# drums.net
KiCad netlist of a schematic drawn in EAGLE
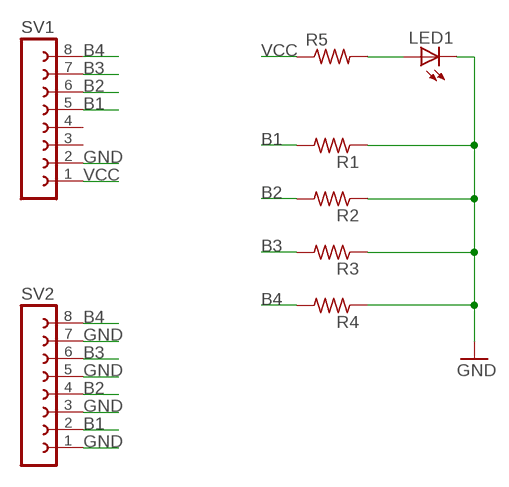
[diagram p0: schematic, sheet 1]

(export (version "E")
  (design (tool "Eeschema 10.0.6"))
  (components
    (comp (ref "LED1")
      (value "LED5MM")
      (footprint "eagle-import:LED5MM")
      (libsource (lib "eagle-import") (part "LED5MM"))
    )
    (comp (ref "R1")
      (value "R-US_0207/7")
      (footprint "eagle-import:0207_7")
      (libsource (lib "eagle-import") (part "R-US_0207/7"))
    )
    (comp (ref "R2")
      (value "R-US_0207/7")
      (footprint "eagle-import:0207_7")
      (libsource (lib "eagle-import") (part "R-US_0207/7"))
    )
    (comp (ref "R3")
      (value "R-US_0207/7")
      (footprint "eagle-import:0207_7")
      (libsource (lib "eagle-import") (part "R-US_0207/7"))
    )
    (comp (ref "R4")
      (value "R-US_0207/7")
      (footprint "eagle-import:0207_7")
      (libsource (lib "eagle-import") (part "R-US_0207/7"))
    )
    (comp (ref "R5")
      (value "R-US_0207/7")
      (footprint "eagle-import:0207_7")
      (libsource (lib "eagle-import") (part "R-US_0207/7"))
    )
    (comp (ref "SV1")
      (value "FE08-1")
      (footprint "eagle-import:FE08")
      (libsource (lib "eagle-import") (part "FE08-1"))
    )
    (comp (ref "SV2")
      (value "FE08-1")
      (footprint "eagle-import:FE08")
      (libsource (lib "eagle-import") (part "FE08-1"))
    )
  )
  (nets
    (net (code "1") (name "/B1") (class "Default")
      (node (ref "R1") (pin "2") (pinfunction "2_2") (pintype "passive"))
      (node (ref "SV1") (pin "5") (pinfunction "5_5") (pintype "passive"))
      (node (ref "SV2") (pin "2") (pinfunction "2_2") (pintype "passive"))
    )
    (net (code "2") (name "/B2") (class "Default")
      (node (ref "R2") (pin "2") (pinfunction "2_2") (pintype "passive"))
      (node (ref "SV1") (pin "6") (pinfunction "6_6") (pintype "passive"))
      (node (ref "SV2") (pin "4") (pinfunction "4_4") (pintype "passive"))
    )
    (net (code "3") (name "/B3") (class "Default")
      (node (ref "R3") (pin "2") (pinfunction "2_2") (pintype "passive"))
      (node (ref "SV1") (pin "7") (pinfunction "7_7") (pintype "passive"))
      (node (ref "SV2") (pin "6") (pinfunction "6_6") (pintype "passive"))
    )
    (net (code "4") (name "/B4") (class "Default")
      (node (ref "R4") (pin "2") (pinfunction "2_2") (pintype "passive"))
      (node (ref "SV1") (pin "8") (pinfunction "8_8") (pintype "passive"))
      (node (ref "SV2") (pin "8") (pinfunction "8_8") (pintype "passive"))
    )
    (net (code "5") (name "/VCC") (class "Default")
      (node (ref "R5") (pin "1") (pinfunction "1_1") (pintype "passive"))
      (node (ref "SV1") (pin "1") (pinfunction "1_1") (pintype "passive"))
    )
    (net (code "6") (name "GND") (class "Default")
      (node (ref "LED1") (pin "K") (pinfunction "C_K") (pintype "passive"))
      (node (ref "R1") (pin "1") (pinfunction "1_1") (pintype "passive"))
      (node (ref "R2") (pin "1") (pinfunction "1_1") (pintype "passive"))
      (node (ref "R3") (pin "1") (pinfunction "1_1") (pintype "passive"))
      (node (ref "R4") (pin "1") (pinfunction "1_1") (pintype "passive"))
      (node (ref "SV1") (pin "2") (pinfunction "2_2") (pintype "passive"))
      (node (ref "SV2") (pin "1") (pinfunction "1_1") (pintype "passive"))
      (node (ref "SV2") (pin "3") (pinfunction "3_3") (pintype "passive"))
      (node (ref "SV2") (pin "5") (pinfunction "5_5") (pintype "passive"))
      (node (ref "SV2") (pin "7") (pinfunction "7_7") (pintype "passive"))
    )
    (net (code "7") (name "Net-(LED1-PadA)") (class "Default")
      (node (ref "LED1") (pin "A") (pinfunction "A_A") (pintype "passive"))
      (node (ref "R5") (pin "2") (pinfunction "2_2") (pintype "passive"))
    )
    (net (code "8") (name "unconnected-(SV1-Pad3)") (class "Default")
      (node (ref "SV1") (pin "3") (pinfunction "3_3") (pintype "passive"))
    )
    (net (code "9") (name "unconnected-(SV1-Pad4)") (class "Default")
      (node (ref "SV1") (pin "4") (pinfunction "4_4") (pintype "passive"))
    )
  )
)
